# ControlModule.net
KiCad netlist of a schematic drawn in EAGLE
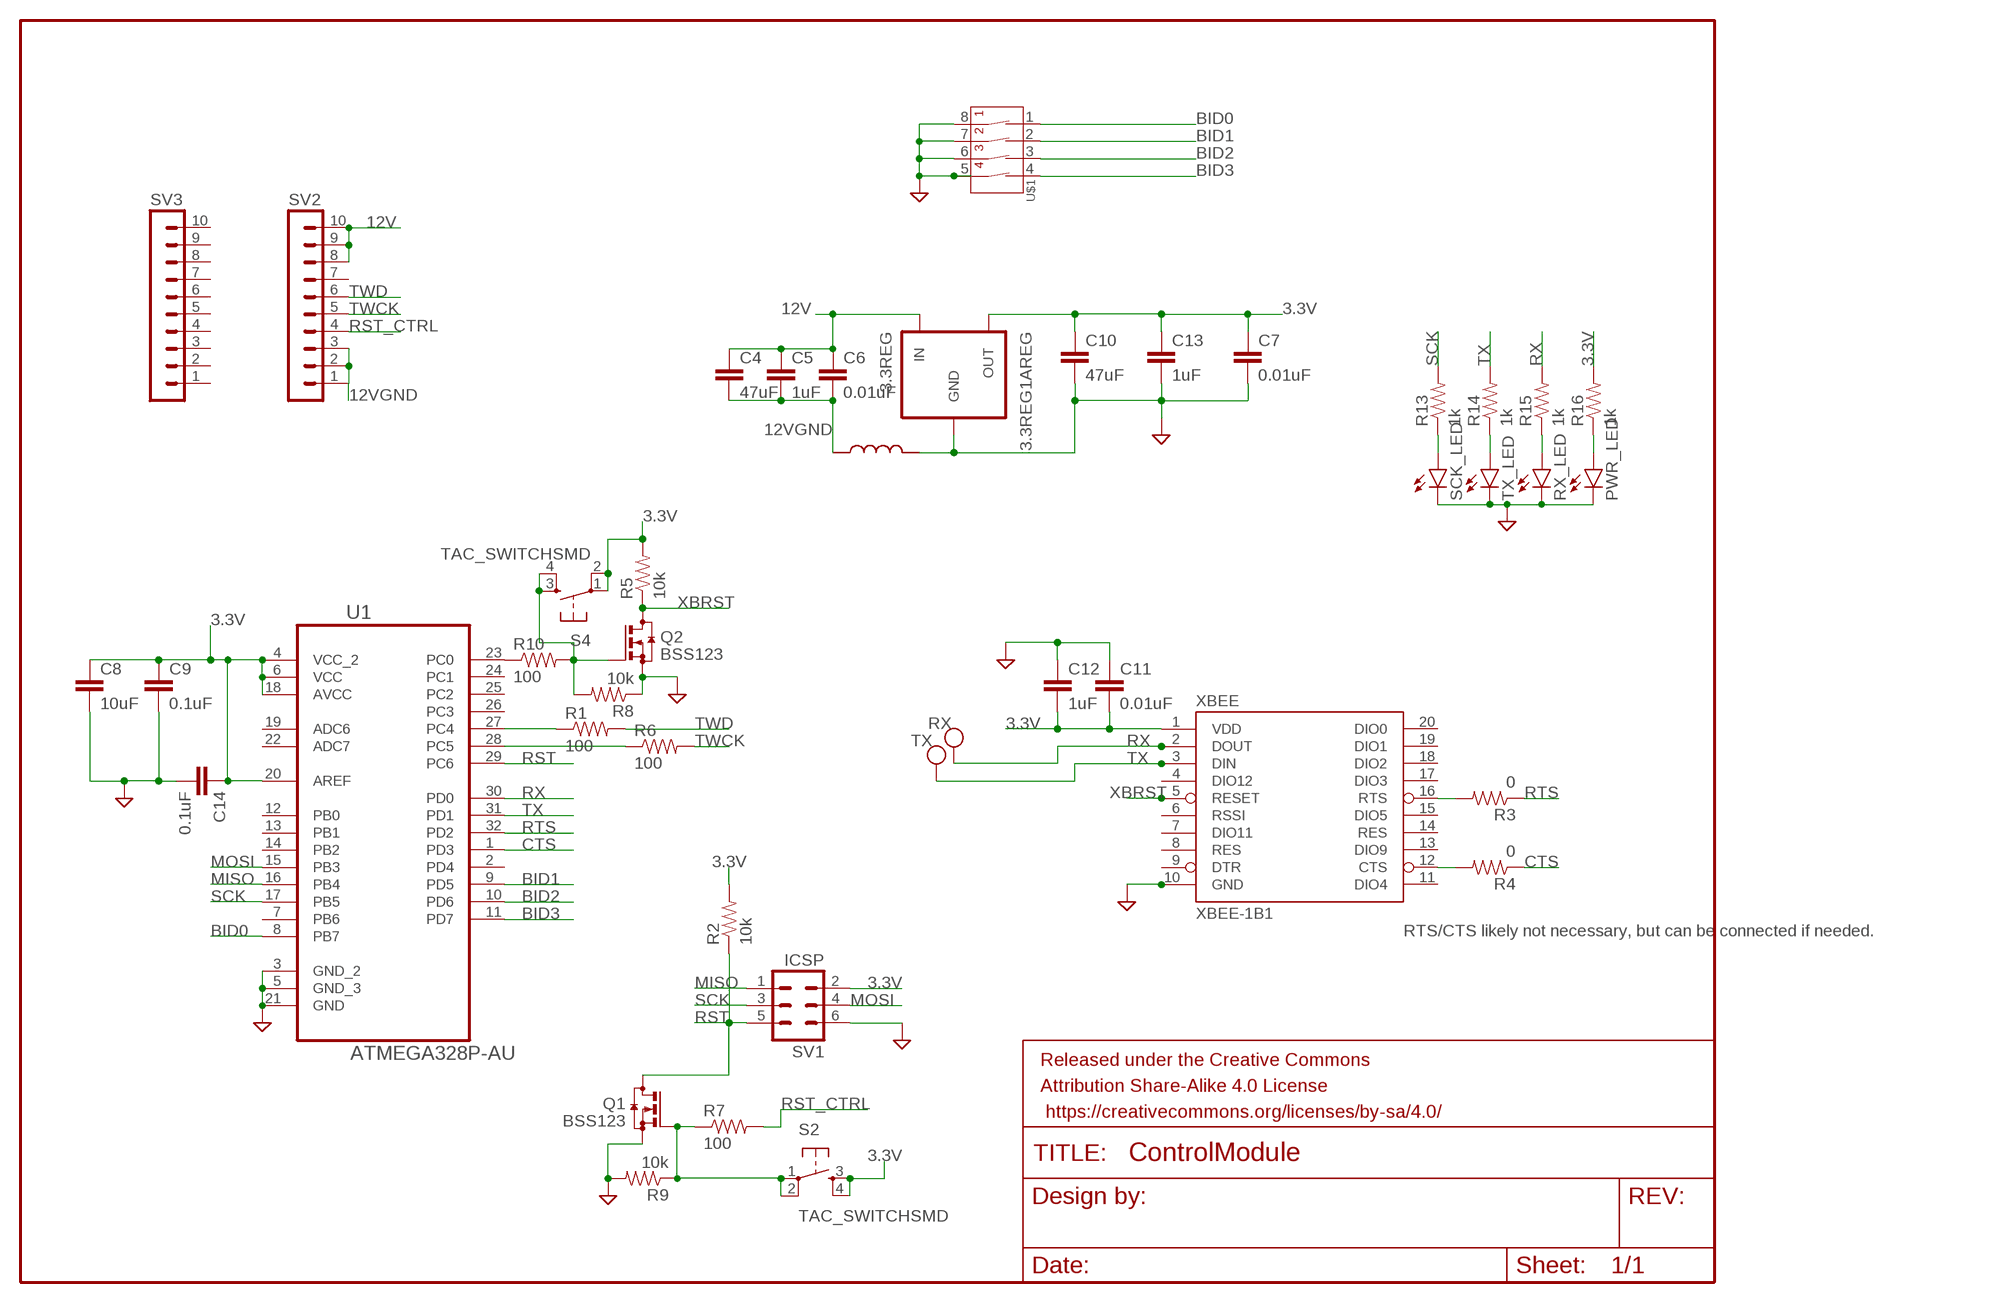
[diagram p0: schematic, sheet 1]

(export (version "E")
  (design (tool "Eeschema 10.0.6"))
  (components
    (comp (ref "3.3REG")
      (value "3.3REG1AREG")
      (footprint "eagle-import:DPAK")
      (libsource (lib "eagle-import") (part "3.3REG1AREG"))
    )
    (comp (ref "C4")
      (value "47uF")
      (footprint "eagle-import:1206")
      (libsource (lib "eagle-import") (part "CAP1206"))
    )
    (comp (ref "C5")
      (value "1uF")
      (footprint "eagle-import:0805")
      (libsource (lib "eagle-import") (part "CAP0805"))
    )
    (comp (ref "C6")
      (value "0.01uF")
      (footprint "eagle-import:0805")
      (libsource (lib "eagle-import") (part "CAP0805"))
    )
    (comp (ref "C7")
      (value "0.01uF")
      (footprint "eagle-import:0805")
      (libsource (lib "eagle-import") (part "CAP0805"))
    )
    (comp (ref "C8")
      (value "10uF")
      (footprint "eagle-import:0805")
      (libsource (lib "eagle-import") (part "CAP0805"))
    )
    (comp (ref "C9")
      (value "0.1uF")
      (footprint "eagle-import:0805")
      (libsource (lib "eagle-import") (part "CAP0805"))
    )
    (comp (ref "C10")
      (value "47uF")
      (footprint "eagle-import:1206")
      (libsource (lib "eagle-import") (part "CAP1206"))
    )
    (comp (ref "C11")
      (value "0.01uF")
      (footprint "eagle-import:0805")
      (libsource (lib "eagle-import") (part "CAP0805"))
    )
    (comp (ref "C12")
      (value "1uF")
      (footprint "eagle-import:0805")
      (libsource (lib "eagle-import") (part "CAP0805"))
    )
    (comp (ref "C13")
      (value "1uF")
      (footprint "eagle-import:0805")
      (libsource (lib "eagle-import") (part "CAP0805"))
    )
    (comp (ref "C14")
      (value "0.1uF")
      (footprint "eagle-import:0805")
      (libsource (lib "eagle-import") (part "CAP0805"))
    )
    (comp (ref "FRAME1")
      (value "FRAME-LETTER")
      (footprint "eagle-import:CREATIVE_COMMONS")
      (libsource (lib "eagle-import") (part "FRAME-LETTER"))
    )
    (comp (ref "PWR_LED")
      (value "LED1206")
      (footprint "eagle-import:LED-1206")
      (libsource (lib "eagle-import") (part "LED1206"))
    )
    (comp (ref "Q1")
      (value "BSS123")
      (footprint "eagle-import:SOT23")
      (libsource (lib "eagle-import") (part "BSS123"))
    )
    (comp (ref "Q2")
      (value "BSS123")
      (footprint "eagle-import:SOT23")
      (libsource (lib "eagle-import") (part "BSS123"))
    )
    (comp (ref "R1")
      (value "100")
      (footprint "eagle-import:0805")
      (libsource (lib "eagle-import") (part "RESISTOR0805-RES"))
    )
    (comp (ref "R2")
      (value "10k")
      (footprint "eagle-import:0805")
      (libsource (lib "eagle-import") (part "RESISTOR0805-RES"))
    )
    (comp (ref "R3")
      (value "0")
      (footprint "eagle-import:0805")
      (libsource (lib "eagle-import") (part "RESISTOR0805-RES"))
    )
    (comp (ref "R4")
      (value "0")
      (footprint "eagle-import:0805")
      (libsource (lib "eagle-import") (part "RESISTOR0805-RES"))
    )
    (comp (ref "R5")
      (value "10k")
      (footprint "eagle-import:0805")
      (libsource (lib "eagle-import") (part "RESISTOR0805-RES"))
    )
    (comp (ref "R6")
      (value "100")
      (footprint "eagle-import:0805")
      (libsource (lib "eagle-import") (part "RESISTOR0805-RES"))
    )
    (comp (ref "R7")
      (value "100")
      (footprint "eagle-import:0805")
      (libsource (lib "eagle-import") (part "RESISTOR0805-RES"))
    )
    (comp (ref "R8")
      (value "10k")
      (footprint "eagle-import:0805")
      (libsource (lib "eagle-import") (part "RESISTOR0805-RES"))
    )
    (comp (ref "R9")
      (value "10k")
      (footprint "eagle-import:0805")
      (libsource (lib "eagle-import") (part "RESISTOR0805-RES"))
    )
    (comp (ref "R10")
      (value "100")
      (footprint "eagle-import:0805")
      (libsource (lib "eagle-import") (part "RESISTOR0805-RES"))
    )
    (comp (ref "R13")
      (value "1k")
      (footprint "eagle-import:0805")
      (libsource (lib "eagle-import") (part "RESISTOR0805-RES"))
    )
    (comp (ref "R14")
      (value "1k")
      (footprint "eagle-import:0805")
      (libsource (lib "eagle-import") (part "RESISTOR0805-RES"))
    )
    (comp (ref "R15")
      (value "1k")
      (footprint "eagle-import:0805")
      (libsource (lib "eagle-import") (part "RESISTOR0805-RES"))
    )
    (comp (ref "R16")
      (value "1k")
      (footprint "eagle-import:0805")
      (libsource (lib "eagle-import") (part "RESISTOR0805-RES"))
    )
    (comp (ref "RX")
      (value "TEST_PT")
      (footprint "eagle-import:TESTING_PT")
      (libsource (lib "eagle-import") (part "TEST_PT"))
    )
    (comp (ref "RX_LED")
      (value "LED1206")
      (footprint "eagle-import:LED-1206")
      (libsource (lib "eagle-import") (part "LED1206"))
    )
    (comp (ref "S2")
      (value "TAC_SWITCHSMD")
      (footprint "eagle-import:TACTILE-SWITCH-SMD")
      (libsource (lib "eagle-import") (part "TAC_SWITCHSMD"))
    )
    (comp (ref "S4")
      (value "TAC_SWITCHSMD")
      (footprint "eagle-import:TACTILE-SWITCH-SMD")
      (libsource (lib "eagle-import") (part "TAC_SWITCHSMD"))
    )
    (comp (ref "SCK_LED")
      (value "LED1206")
      (footprint "eagle-import:LED-1206")
      (libsource (lib "eagle-import") (part "LED1206"))
    )
    (comp (ref "SV1")
      (value "ICSP")
      (footprint "eagle-import:MA03-2")
      (libsource (lib "eagle-import") (part "MA03-2"))
    )
    (comp (ref "SV2")
      (value "MA10-1W")
      (footprint "eagle-import:MA10-1W")
      (libsource (lib "eagle-import") (part "MA10-1W"))
    )
    (comp (ref "SV3")
      (value "MA10-1W")
      (footprint "eagle-import:MA10-1W")
      (libsource (lib "eagle-import") (part "MA10-1W"))
    )
    (comp (ref "TX")
      (value "TEST_PT")
      (footprint "eagle-import:TESTING_PT")
      (libsource (lib "eagle-import") (part "TEST_PT"))
    )
    (comp (ref "TX_LED")
      (value "LED1206")
      (footprint "eagle-import:LED-1206")
      (libsource (lib "eagle-import") (part "LED1206"))
    )
    (comp (ref "U$1")
      (value "4-POS-DIP")
      (footprint "eagle-import:4-POS-DIP-SMD")
      (libsource (lib "eagle-import") (part "4-POS-DIP"))
    )
    (comp (ref "U$2")
      (value "INDUCTOR")
      (footprint "eagle-import:0805")
      (libsource (lib "eagle-import") (part "INDUCTOR"))
    )
    (comp (ref "U1")
      (value "ATMEGA328P-AU")
      (footprint "eagle-import:QFP80P900X900X120-32N")
      (libsource (lib "eagle-import") (part "ATMEGA328P-AU"))
    )
    (comp (ref "XBEE")
      (value "XBEE-1B1")
      (footprint "eagle-import:XBEE-1")
      (libsource (lib "eagle-import") (part "XBEE-1B1"))
    )
  )
  (nets
    (net (code "1") (name "/3.3V") (class "Default")
      (node (ref "3.3REG") (pin "SOURCE") (pinfunction "OUT_SOURCE") (pintype "bidirectional"))
      (node (ref "C10") (pin "1") (pinfunction "1_1") (pintype "passive"))
      (node (ref "C11") (pin "2") (pinfunction "2_2") (pintype "passive"))
      (node (ref "C12") (pin "2") (pinfunction "2_2") (pintype "passive"))
      (node (ref "C13") (pin "1") (pinfunction "1_1") (pintype "passive"))
      (node (ref "C14") (pin "1") (pinfunction "1_1") (pintype "passive"))
      (node (ref "C7") (pin "1") (pinfunction "1_1") (pintype "passive"))
      (node (ref "C8") (pin "1") (pinfunction "1_1") (pintype "passive"))
      (node (ref "C9") (pin "1") (pinfunction "1_1") (pintype "passive"))
      (node (ref "R16") (pin "2") (pinfunction "2_2") (pintype "passive"))
      (node (ref "R2") (pin "2") (pinfunction "2_2") (pintype "passive"))
      (node (ref "R5") (pin "2") (pinfunction "2_2") (pintype "passive"))
      (node (ref "S2") (pin "3") (pinfunction "3_3") (pintype "passive"))
      (node (ref "S2") (pin "4") (pinfunction "4_4") (pintype "passive"))
      (node (ref "S4") (pin "1") (pinfunction "1_1") (pintype "passive"))
      (node (ref "S4") (pin "2") (pinfunction "2_2") (pintype "passive"))
      (node (ref "SV1") (pin "2") (pinfunction "2_2") (pintype "passive"))
      (node (ref "U1") (pin "18") (pinfunction "AVCC_18") (pintype "power_in"))
      (node (ref "U1") (pin "20") (pinfunction "AREF_20") (pintype "input"))
      (node (ref "U1") (pin "4") (pinfunction "VCC_2_4") (pintype "power_in"))
      (node (ref "U1") (pin "6") (pinfunction "VCC_6") (pintype "power_in"))
      (node (ref "XBEE") (pin "1") (pinfunction "VDD_1") (pintype "power_in"))
    )
    (net (code "2") (name "/12V") (class "Default")
      (node (ref "3.3REG") (pin "GATE") (pinfunction "IN_GATE") (pintype "input"))
      (node (ref "C4") (pin "1") (pinfunction "1_1") (pintype "passive"))
      (node (ref "C5") (pin "1") (pinfunction "1_1") (pintype "passive"))
      (node (ref "C6") (pin "1") (pinfunction "1_1") (pintype "passive"))
      (node (ref "SV2") (pin "10") (pinfunction "10_10") (pintype "passive"))
      (node (ref "SV2") (pin "8") (pinfunction "8_8") (pintype "passive"))
      (node (ref "SV2") (pin "9") (pinfunction "9_9") (pintype "passive"))
    )
    (net (code "3") (name "/12VGND") (class "Default")
      (node (ref "C4") (pin "2") (pinfunction "2_2") (pintype "passive"))
      (node (ref "C5") (pin "2") (pinfunction "2_2") (pintype "passive"))
      (node (ref "C6") (pin "2") (pinfunction "2_2") (pintype "passive"))
      (node (ref "SV2") (pin "1") (pinfunction "1_1") (pintype "passive"))
      (node (ref "SV2") (pin "2") (pinfunction "2_2") (pintype "passive"))
      (node (ref "SV2") (pin "3") (pinfunction "3_3") (pintype "passive"))
      (node (ref "U$2") (pin "1") (pinfunction "P$1_1") (pintype "bidirectional"))
    )
    (net (code "4") (name "/BID0") (class "Default")
      (node (ref "U$1") (pin "1") (pinfunction "1A_1") (pintype "bidirectional"))
      (node (ref "U1") (pin "8") (pinfunction "PB7_8") (pintype "bidirectional"))
    )
    (net (code "5") (name "/BID1") (class "Default")
      (node (ref "U$1") (pin "2") (pinfunction "2A_2") (pintype "bidirectional"))
      (node (ref "U1") (pin "9") (pinfunction "PD5_9") (pintype "bidirectional"))
    )
    (net (code "6") (name "/BID2") (class "Default")
      (node (ref "U$1") (pin "3") (pinfunction "3A_3") (pintype "bidirectional"))
      (node (ref "U1") (pin "10") (pinfunction "PD6_10") (pintype "bidirectional"))
    )
    (net (code "7") (name "/BID3") (class "Default")
      (node (ref "U$1") (pin "4") (pinfunction "4A_4") (pintype "bidirectional"))
      (node (ref "U1") (pin "11") (pinfunction "PD7_11") (pintype "bidirectional"))
    )
    (net (code "8") (name "/CTS") (class "Default")
      (node (ref "R4") (pin "1") (pinfunction "1_1") (pintype "passive"))
      (node (ref "U1") (pin "1") (pinfunction "PD3_1") (pintype "bidirectional"))
    )
    (net (code "9") (name "/MISO") (class "Default")
      (node (ref "SV1") (pin "1") (pinfunction "1_1") (pintype "passive"))
      (node (ref "U1") (pin "16") (pinfunction "PB4_16") (pintype "bidirectional"))
    )
    (net (code "10") (name "/MOSI") (class "Default")
      (node (ref "SV1") (pin "4") (pinfunction "4_4") (pintype "passive"))
      (node (ref "U1") (pin "15") (pinfunction "PB3_15") (pintype "bidirectional"))
    )
    (net (code "11") (name "/RST") (class "Default")
      (node (ref "Q1") (pin "3") (pinfunction "D_3") (pintype "passive"))
      (node (ref "R2") (pin "1") (pinfunction "1_1") (pintype "passive"))
      (node (ref "SV1") (pin "5") (pinfunction "5_5") (pintype "passive"))
      (node (ref "U1") (pin "29") (pinfunction "PC6_29") (pintype "bidirectional"))
    )
    (net (code "12") (name "/RST_CTRL") (class "Default")
      (node (ref "R7") (pin "2") (pinfunction "2_2") (pintype "passive"))
      (node (ref "SV2") (pin "4") (pinfunction "4_4") (pintype "passive"))
    )
    (net (code "13") (name "/RTS") (class "Default")
      (node (ref "R3") (pin "1") (pinfunction "1_1") (pintype "passive"))
      (node (ref "U1") (pin "32") (pinfunction "PD2_32") (pintype "bidirectional"))
    )
    (net (code "14") (name "/RX") (class "Default")
      (node (ref "R15") (pin "2") (pinfunction "2_2") (pintype "passive"))
      (node (ref "RX") (pin "P$1") (pinfunction "P$1_P$1") (pintype "bidirectional"))
      (node (ref "U1") (pin "30") (pinfunction "PD0_30") (pintype "bidirectional"))
      (node (ref "XBEE") (pin "2") (pinfunction "DOUT_2") (pintype "output"))
    )
    (net (code "15") (name "/SCK") (class "Default")
      (node (ref "R13") (pin "2") (pinfunction "2_2") (pintype "passive"))
      (node (ref "SV1") (pin "3") (pinfunction "3_3") (pintype "passive"))
      (node (ref "U1") (pin "17") (pinfunction "PB5_17") (pintype "bidirectional"))
    )
    (net (code "16") (name "/TWCK") (class "Default")
      (node (ref "R6") (pin "2") (pinfunction "2_2") (pintype "passive"))
      (node (ref "SV2") (pin "5") (pinfunction "5_5") (pintype "passive"))
    )
    (net (code "17") (name "/TWD") (class "Default")
      (node (ref "R1") (pin "2") (pinfunction "2_2") (pintype "passive"))
      (node (ref "SV2") (pin "6") (pinfunction "6_6") (pintype "passive"))
    )
    (net (code "18") (name "/TX") (class "Default")
      (node (ref "R14") (pin "2") (pinfunction "2_2") (pintype "passive"))
      (node (ref "TX") (pin "P$1") (pinfunction "P$1_P$1") (pintype "bidirectional"))
      (node (ref "U1") (pin "31") (pinfunction "PD1_31") (pintype "bidirectional"))
      (node (ref "XBEE") (pin "3") (pinfunction "DIN_3") (pintype "input"))
    )
    (net (code "19") (name "/XBRST") (class "Default")
      (node (ref "Q2") (pin "3") (pinfunction "D_3") (pintype "passive"))
      (node (ref "R5") (pin "1") (pinfunction "1_1") (pintype "passive"))
      (node (ref "XBEE") (pin "5") (pinfunction "RESET_5") (pintype "input"))
    )
    (net (code "20") (name "GND") (class "Default")
      (node (ref "3.3REG") (pin "DRAIN") (pinfunction "GND_DRAIN") (pintype "bidirectional"))
      (node (ref "C10") (pin "2") (pinfunction "2_2") (pintype "passive"))
      (node (ref "C11") (pin "1") (pinfunction "1_1") (pintype "passive"))
      (node (ref "C12") (pin "1") (pinfunction "1_1") (pintype "passive"))
      (node (ref "C13") (pin "2") (pinfunction "2_2") (pintype "passive"))
      (node (ref "C14") (pin "2") (pinfunction "2_2") (pintype "passive"))
      (node (ref "C7") (pin "2") (pinfunction "2_2") (pintype "passive"))
      (node (ref "C8") (pin "2") (pinfunction "2_2") (pintype "passive"))
      (node (ref "C9") (pin "2") (pinfunction "2_2") (pintype "passive"))
      (node (ref "PWR_LED") (pin "C") (pinfunction "C_C") (pintype "passive"))
      (node (ref "Q1") (pin "2") (pinfunction "S_2") (pintype "passive"))
      (node (ref "Q2") (pin "2") (pinfunction "S_2") (pintype "passive"))
      (node (ref "R8") (pin "1") (pinfunction "1_1") (pintype "passive"))
      (node (ref "R9") (pin "2") (pinfunction "2_2") (pintype "passive"))
      (node (ref "RX_LED") (pin "C") (pinfunction "C_C") (pintype "passive"))
      (node (ref "SCK_LED") (pin "C") (pinfunction "C_C") (pintype "passive"))
      (node (ref "SV1") (pin "6") (pinfunction "6_6") (pintype "passive"))
      (node (ref "TX_LED") (pin "C") (pinfunction "C_C") (pintype "passive"))
      (node (ref "U$1") (pin "5") (pinfunction "4B_5") (pintype "bidirectional"))
      (node (ref "U$1") (pin "6") (pinfunction "3B_6") (pintype "bidirectional"))
      (node (ref "U$1") (pin "7") (pinfunction "2B_7") (pintype "bidirectional"))
      (node (ref "U$1") (pin "8") (pinfunction "1B_8") (pintype "bidirectional"))
      (node (ref "U$2") (pin "2") (pinfunction "P$2_2") (pintype "bidirectional"))
      (node (ref "U1") (pin "21") (pinfunction "GND_21") (pintype "passive"))
      (node (ref "U1") (pin "3") (pinfunction "GND_2_3") (pintype "passive"))
      (node (ref "U1") (pin "5") (pinfunction "GND_3_5") (pintype "passive"))
      (node (ref "XBEE") (pin "10") (pinfunction "GND_10") (pintype "power_in"))
    )
    (net (code "21") (name "Net-(PWR_LED-PadA)") (class "Default")
      (node (ref "PWR_LED") (pin "A") (pinfunction "A_A") (pintype "passive"))
      (node (ref "R16") (pin "1") (pinfunction "1_1") (pintype "passive"))
    )
    (net (code "22") (name "Net-(Q1-G)") (class "Default")
      (node (ref "Q1") (pin "1") (pinfunction "G_1") (pintype "passive"))
      (node (ref "R7") (pin "1") (pinfunction "1_1") (pintype "passive"))
      (node (ref "R9") (pin "1") (pinfunction "1_1") (pintype "passive"))
      (node (ref "S2") (pin "1") (pinfunction "1_1") (pintype "passive"))
      (node (ref "S2") (pin "2") (pinfunction "2_2") (pintype "passive"))
    )
    (net (code "23") (name "Net-(Q2-G)") (class "Default")
      (node (ref "Q2") (pin "1") (pinfunction "G_1") (pintype "passive"))
      (node (ref "R10") (pin "2") (pinfunction "2_2") (pintype "passive"))
      (node (ref "R8") (pin "2") (pinfunction "2_2") (pintype "passive"))
      (node (ref "S4") (pin "3") (pinfunction "3_3") (pintype "passive"))
      (node (ref "S4") (pin "4") (pinfunction "4_4") (pintype "passive"))
    )
    (net (code "24") (name "Net-(R13-Pad1)") (class "Default")
      (node (ref "R13") (pin "1") (pinfunction "1_1") (pintype "passive"))
      (node (ref "SCK_LED") (pin "A") (pinfunction "A_A") (pintype "passive"))
    )
    (net (code "25") (name "Net-(R14-Pad1)") (class "Default")
      (node (ref "R14") (pin "1") (pinfunction "1_1") (pintype "passive"))
      (node (ref "TX_LED") (pin "A") (pinfunction "A_A") (pintype "passive"))
    )
    (net (code "26") (name "Net-(R15-Pad1)") (class "Default")
      (node (ref "R15") (pin "1") (pinfunction "1_1") (pintype "passive"))
      (node (ref "RX_LED") (pin "A") (pinfunction "A_A") (pintype "passive"))
    )
    (net (code "27") (name "Net-(U1-PC0)") (class "Default")
      (node (ref "R10") (pin "1") (pinfunction "1_1") (pintype "passive"))
      (node (ref "U1") (pin "23") (pinfunction "PC0_23") (pintype "bidirectional"))
    )
    (net (code "28") (name "Net-(U1-PC4)") (class "Default")
      (node (ref "R1") (pin "1") (pinfunction "1_1") (pintype "passive"))
      (node (ref "U1") (pin "27") (pinfunction "PC4_27") (pintype "bidirectional"))
    )
    (net (code "29") (name "Net-(U1-PC5)") (class "Default")
      (node (ref "R6") (pin "1") (pinfunction "1_1") (pintype "passive"))
      (node (ref "U1") (pin "28") (pinfunction "PC5_28") (pintype "bidirectional"))
    )
    (net (code "30") (name "Net-(XBEE-CTS)") (class "Default")
      (node (ref "R4") (pin "2") (pinfunction "2_2") (pintype "passive"))
      (node (ref "XBEE") (pin "12") (pinfunction "CTS_12") (pintype "output"))
    )
    (net (code "31") (name "Net-(XBEE-RTS)") (class "Default")
      (node (ref "R3") (pin "2") (pinfunction "2_2") (pintype "passive"))
      (node (ref "XBEE") (pin "16") (pinfunction "RTS_16") (pintype "input"))
    )
    (net (code "32") (name "unconnected-(SV2-Pad7)") (class "Default")
      (node (ref "SV2") (pin "7") (pinfunction "7_7") (pintype "passive"))
    )
    (net (code "33") (name "unconnected-(SV3-Pad1)") (class "Default")
      (node (ref "SV3") (pin "1") (pinfunction "1_1") (pintype "passive"))
    )
    (net (code "34") (name "unconnected-(SV3-Pad2)") (class "Default")
      (node (ref "SV3") (pin "2") (pinfunction "2_2") (pintype "passive"))
    )
    (net (code "35") (name "unconnected-(SV3-Pad3)") (class "Default")
      (node (ref "SV3") (pin "3") (pinfunction "3_3") (pintype "passive"))
    )
    (net (code "36") (name "unconnected-(SV3-Pad4)") (class "Default")
      (node (ref "SV3") (pin "4") (pinfunction "4_4") (pintype "passive"))
    )
    (net (code "37") (name "unconnected-(SV3-Pad5)") (class "Default")
      (node (ref "SV3") (pin "5") (pinfunction "5_5") (pintype "passive"))
    )
    (net (code "38") (name "unconnected-(SV3-Pad6)") (class "Default")
      (node (ref "SV3") (pin "6") (pinfunction "6_6") (pintype "passive"))
    )
    (net (code "39") (name "unconnected-(SV3-Pad7)") (class "Default")
      (node (ref "SV3") (pin "7") (pinfunction "7_7") (pintype "passive"))
    )
    (net (code "40") (name "unconnected-(SV3-Pad8)") (class "Default")
      (node (ref "SV3") (pin "8") (pinfunction "8_8") (pintype "passive"))
    )
    (net (code "41") (name "unconnected-(SV3-Pad9)") (class "Default")
      (node (ref "SV3") (pin "9") (pinfunction "9_9") (pintype "passive"))
    )
    (net (code "42") (name "unconnected-(SV3-Pad10)") (class "Default")
      (node (ref "SV3") (pin "10") (pinfunction "10_10") (pintype "passive"))
    )
    (net (code "43") (name "unconnected-(U1-ADC6-Pad19)") (class "Default")
      (node (ref "U1") (pin "19") (pinfunction "ADC6_19") (pintype "input"))
    )
    (net (code "44") (name "unconnected-(U1-ADC7-Pad22)") (class "Default")
      (node (ref "U1") (pin "22") (pinfunction "ADC7_22") (pintype "input"))
    )
    (net (code "45") (name "unconnected-(U1-PB0-Pad12)") (class "Default")
      (node (ref "U1") (pin "12") (pinfunction "PB0_12") (pintype "bidirectional"))
    )
    (net (code "46") (name "unconnected-(U1-PB1-Pad13)") (class "Default")
      (node (ref "U1") (pin "13") (pinfunction "PB1_13") (pintype "bidirectional"))
    )
    (net (code "47") (name "unconnected-(U1-PB2-Pad14)") (class "Default")
      (node (ref "U1") (pin "14") (pinfunction "PB2_14") (pintype "bidirectional"))
    )
    (net (code "48") (name "unconnected-(U1-PB6-Pad7)") (class "Default")
      (node (ref "U1") (pin "7") (pinfunction "PB6_7") (pintype "bidirectional"))
    )
    (net (code "49") (name "unconnected-(U1-PC1-Pad24)") (class "Default")
      (node (ref "U1") (pin "24") (pinfunction "PC1_24") (pintype "bidirectional"))
    )
    (net (code "50") (name "unconnected-(U1-PC2-Pad25)") (class "Default")
      (node (ref "U1") (pin "25") (pinfunction "PC2_25") (pintype "bidirectional"))
    )
    (net (code "51") (name "unconnected-(U1-PC3-Pad26)") (class "Default")
      (node (ref "U1") (pin "26") (pinfunction "PC3_26") (pintype "bidirectional"))
    )
    (net (code "52") (name "unconnected-(U1-PD4-Pad2)") (class "Default")
      (node (ref "U1") (pin "2") (pinfunction "PD4_2") (pintype "bidirectional"))
    )
    (net (code "53") (name "unconnected-(XBEE-DIO0-Pad20)") (class "Default")
      (node (ref "XBEE") (pin "20") (pinfunction "DIO0_20") (pintype "bidirectional"))
    )
    (net (code "54") (name "unconnected-(XBEE-DIO1-Pad19)") (class "Default")
      (node (ref "XBEE") (pin "19") (pinfunction "DIO1_19") (pintype "bidirectional"))
    )
    (net (code "55") (name "unconnected-(XBEE-DIO2-Pad18)") (class "Default")
      (node (ref "XBEE") (pin "18") (pinfunction "DIO2_18") (pintype "bidirectional"))
    )
    (net (code "56") (name "unconnected-(XBEE-DIO3-Pad17)") (class "Default")
      (node (ref "XBEE") (pin "17") (pinfunction "DIO3_17") (pintype "bidirectional"))
    )
    (net (code "57") (name "unconnected-(XBEE-DIO4-Pad11)") (class "Default")
      (node (ref "XBEE") (pin "11") (pinfunction "DIO4_11") (pintype "bidirectional"))
    )
    (net (code "58") (name "unconnected-(XBEE-DIO5-Pad15)") (class "Default")
      (node (ref "XBEE") (pin "15") (pinfunction "DIO5_15") (pintype "bidirectional"))
    )
    (net (code "59") (name "unconnected-(XBEE-DIO9-Pad13)") (class "Default")
      (node (ref "XBEE") (pin "13") (pinfunction "DIO9_13") (pintype "bidirectional"))
    )
    (net (code "60") (name "unconnected-(XBEE-DIO11-Pad7)") (class "Default")
      (node (ref "XBEE") (pin "7") (pinfunction "DIO11_7") (pintype "bidirectional"))
    )
    (net (code "61") (name "unconnected-(XBEE-DIO12-Pad4)") (class "Default")
      (node (ref "XBEE") (pin "4") (pinfunction "DIO12_4") (pintype "bidirectional"))
    )
    (net (code "62") (name "unconnected-(XBEE-DTR-Pad9)") (class "Default")
      (node (ref "XBEE") (pin "9") (pinfunction "DTR_9") (pintype "bidirectional"))
    )
    (net (code "63") (name "unconnected-(XBEE-RES-Pad8)") (class "Default")
      (node (ref "XBEE") (pin "8") (pinfunction "RES_8") (pintype "bidirectional"))
    )
    (net (code "64") (name "unconnected-(XBEE-RES-Pad14)") (class "Default")
      (node (ref "XBEE") (pin "14") (pinfunction "RES_14") (pintype "bidirectional"))
    )
    (net (code "65") (name "unconnected-(XBEE-RSSI-Pad6)") (class "Default")
      (node (ref "XBEE") (pin "6") (pinfunction "RSSI_6") (pintype "bidirectional"))
    )
  )
)
